# capsenseboard.net
KiCad netlist of a schematic drawn in EAGLE
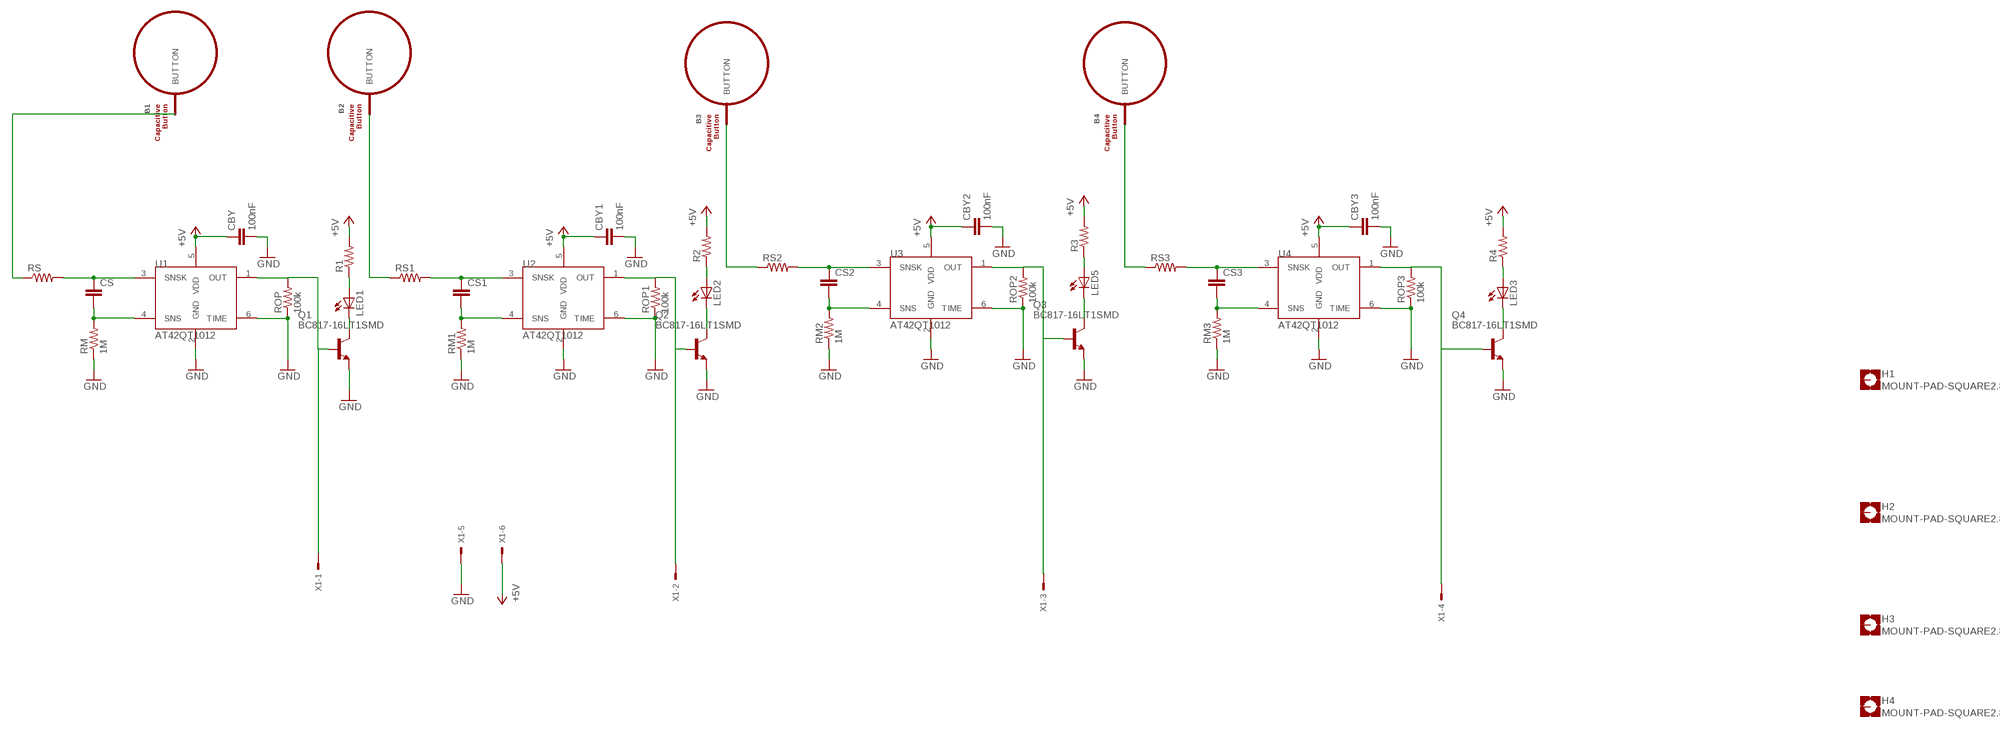
[diagram p0: schematic, sheet 1]

(export (version "E")
  (design (tool "Eeschema 10.0.6"))
  (components
    (comp (ref "B1")
      (value "BUTTON_PASSIVE12MM")
      (footprint "eagle-import:BUTTON_PASSIVE_12MM")
      (libsource (lib "eagle-import") (part "BUTTON_PASSIVE12MM"))
    )
    (comp (ref "B2")
      (value "BUTTON_PASSIVE12MM")
      (footprint "eagle-import:BUTTON_PASSIVE_12MM")
      (libsource (lib "eagle-import") (part "BUTTON_PASSIVE12MM"))
    )
    (comp (ref "B3")
      (value "BUTTON_PASSIVE12MM")
      (footprint "eagle-import:BUTTON_PASSIVE_12MM")
      (libsource (lib "eagle-import") (part "BUTTON_PASSIVE12MM"))
    )
    (comp (ref "B4")
      (value "BUTTON_PASSIVE12MM")
      (footprint "eagle-import:BUTTON_PASSIVE_12MM")
      (libsource (lib "eagle-import") (part "BUTTON_PASSIVE12MM"))
    )
    (comp (ref "CBY")
      (value "100nF")
      (footprint "eagle-import:C1206K")
      (libsource (lib "eagle-import") (part "C-EUC1206K"))
    )
    (comp (ref "CBY1")
      (value "100nF")
      (footprint "eagle-import:C1206K")
      (libsource (lib "eagle-import") (part "C-EUC1206K"))
    )
    (comp (ref "CBY2")
      (value "100nF")
      (footprint "eagle-import:C1206K")
      (libsource (lib "eagle-import") (part "C-EUC1206K"))
    )
    (comp (ref "CBY3")
      (value "100nF")
      (footprint "eagle-import:C1206K")
      (libsource (lib "eagle-import") (part "C-EUC1206K"))
    )
    (comp (ref "CS")
      (value "C-EUC1206K")
      (footprint "eagle-import:C1206K")
      (libsource (lib "eagle-import") (part "C-EUC1206K"))
    )
    (comp (ref "CS1")
      (value "C-EUC1206K")
      (footprint "eagle-import:C1206K")
      (libsource (lib "eagle-import") (part "C-EUC1206K"))
    )
    (comp (ref "CS2")
      (value "C-EUC1206K")
      (footprint "eagle-import:C1206K")
      (libsource (lib "eagle-import") (part "C-EUC1206K"))
    )
    (comp (ref "CS3")
      (value "C-EUC1206K")
      (footprint "eagle-import:C1206K")
      (libsource (lib "eagle-import") (part "C-EUC1206K"))
    )
    (comp (ref "H1")
      (value "MOUNT-PAD-SQUARE2.8")
      (footprint "eagle-import:2,8-PAD-SQUARE")
      (libsource (lib "eagle-import") (part "MOUNT-PAD-SQUARE2.8"))
    )
    (comp (ref "H2")
      (value "MOUNT-PAD-SQUARE2.8")
      (footprint "eagle-import:2,8-PAD-SQUARE")
      (libsource (lib "eagle-import") (part "MOUNT-PAD-SQUARE2.8"))
    )
    (comp (ref "H3")
      (value "MOUNT-PAD-SQUARE2.8")
      (footprint "eagle-import:2,8-PAD-SQUARE")
      (libsource (lib "eagle-import") (part "MOUNT-PAD-SQUARE2.8"))
    )
    (comp (ref "H4")
      (value "MOUNT-PAD-SQUARE2.8")
      (footprint "eagle-import:2,8-PAD-SQUARE")
      (libsource (lib "eagle-import") (part "MOUNT-PAD-SQUARE2.8"))
    )
    (comp (ref "LED1")
      (value "LEDCHIPLED_1206")
      (footprint "eagle-import:CHIPLED_1206")
      (libsource (lib "eagle-import") (part "LEDCHIPLED_1206"))
    )
    (comp (ref "LED2")
      (value "LEDCHIPLED_1206")
      (footprint "eagle-import:CHIPLED_1206")
      (libsource (lib "eagle-import") (part "LEDCHIPLED_1206"))
    )
    (comp (ref "LED3")
      (value "LEDCHIPLED_1206")
      (footprint "eagle-import:CHIPLED_1206")
      (libsource (lib "eagle-import") (part "LEDCHIPLED_1206"))
    )
    (comp (ref "LED5")
      (value "LEDCHIPLED_1206")
      (footprint "eagle-import:CHIPLED_1206")
      (libsource (lib "eagle-import") (part "LEDCHIPLED_1206"))
    )
    (comp (ref "Q1")
      (value "BC817-16LT1SMD")
      (footprint "eagle-import:SOT23-BEC")
      (libsource (lib "eagle-import") (part "BC817SMD-16LT1"))
    )
    (comp (ref "Q2")
      (value "BC817-16LT1SMD")
      (footprint "eagle-import:SOT23-BEC")
      (libsource (lib "eagle-import") (part "BC817SMD-16LT1"))
    )
    (comp (ref "Q3")
      (value "BC817-16LT1SMD")
      (footprint "eagle-import:SOT23-BEC")
      (libsource (lib "eagle-import") (part "BC817SMD-16LT1"))
    )
    (comp (ref "Q4")
      (value "BC817-16LT1SMD")
      (footprint "eagle-import:SOT23-BEC")
      (libsource (lib "eagle-import") (part "BC817SMD-16LT1"))
    )
    (comp (ref "R1")
      (value "R-US_R1206")
      (footprint "eagle-import:R1206")
      (libsource (lib "eagle-import") (part "R-US_R1206"))
    )
    (comp (ref "R2")
      (value "R-US_R1206")
      (footprint "eagle-import:R1206")
      (libsource (lib "eagle-import") (part "R-US_R1206"))
    )
    (comp (ref "R3")
      (value "R-US_R1206")
      (footprint "eagle-import:R1206")
      (libsource (lib "eagle-import") (part "R-US_R1206"))
    )
    (comp (ref "R4")
      (value "R-US_R1206")
      (footprint "eagle-import:R1206")
      (libsource (lib "eagle-import") (part "R-US_R1206"))
    )
    (comp (ref "RM")
      (value "1M")
      (footprint "eagle-import:R1206")
      (libsource (lib "eagle-import") (part "R-US_R1206"))
    )
    (comp (ref "RM1")
      (value "1M")
      (footprint "eagle-import:R1206")
      (libsource (lib "eagle-import") (part "R-US_R1206"))
    )
    (comp (ref "RM2")
      (value "1M")
      (footprint "eagle-import:R1206")
      (libsource (lib "eagle-import") (part "R-US_R1206"))
    )
    (comp (ref "RM3")
      (value "1M")
      (footprint "eagle-import:R1206")
      (libsource (lib "eagle-import") (part "R-US_R1206"))
    )
    (comp (ref "ROP")
      (value "100k")
      (footprint "eagle-import:R1206")
      (libsource (lib "eagle-import") (part "R-US_R1206"))
    )
    (comp (ref "ROP1")
      (value "100k")
      (footprint "eagle-import:R1206")
      (libsource (lib "eagle-import") (part "R-US_R1206"))
    )
    (comp (ref "ROP2")
      (value "100k")
      (footprint "eagle-import:R1206")
      (libsource (lib "eagle-import") (part "R-US_R1206"))
    )
    (comp (ref "ROP3")
      (value "100k")
      (footprint "eagle-import:R1206")
      (libsource (lib "eagle-import") (part "R-US_R1206"))
    )
    (comp (ref "RS")
      (value "R-US_R1206")
      (footprint "eagle-import:R1206")
      (libsource (lib "eagle-import") (part "R-US_R1206"))
    )
    (comp (ref "RS1")
      (value "R-US_R1206")
      (footprint "eagle-import:R1206")
      (libsource (lib "eagle-import") (part "R-US_R1206"))
    )
    (comp (ref "RS2")
      (value "R-US_R1206")
      (footprint "eagle-import:R1206")
      (libsource (lib "eagle-import") (part "R-US_R1206"))
    )
    (comp (ref "RS3")
      (value "R-US_R1206")
      (footprint "eagle-import:R1206")
      (libsource (lib "eagle-import") (part "R-US_R1206"))
    )
    (comp (ref "U1")
      (value "AT42QT1012")
      (footprint "eagle-import:SOT-23-6")
      (libsource (lib "eagle-import") (part "AT42QT1012"))
    )
    (comp (ref "U2")
      (value "AT42QT1012")
      (footprint "eagle-import:SOT-23-6")
      (libsource (lib "eagle-import") (part "AT42QT1012"))
    )
    (comp (ref "U3")
      (value "AT42QT1012")
      (footprint "eagle-import:SOT-23-6")
      (libsource (lib "eagle-import") (part "AT42QT1012"))
    )
    (comp (ref "U4")
      (value "AT42QT1012")
      (footprint "eagle-import:SOT-23-6")
      (libsource (lib "eagle-import") (part "AT42QT1012"))
    )
    (comp (ref "X1")
      (value "22-23-2061")
      (footprint "eagle-import:22-23-2061")
      (fields (field (name "MF") "MOLEX"))
      (libsource (lib "eagle-import") (part "22-23-2061"))
    )
  )
  (nets
    (net (code "1") (name "+5V") (class "Default")
      (node (ref "CBY") (pin "1") (pinfunction "1_1") (pintype "passive"))
      (node (ref "CBY1") (pin "1") (pinfunction "1_1") (pintype "passive"))
      (node (ref "CBY2") (pin "1") (pinfunction "1_1") (pintype "passive"))
      (node (ref "CBY3") (pin "1") (pinfunction "1_1") (pintype "passive"))
      (node (ref "R1") (pin "2") (pinfunction "2_2") (pintype "passive"))
      (node (ref "R2") (pin "2") (pinfunction "2_2") (pintype "passive"))
      (node (ref "R3") (pin "2") (pinfunction "2_2") (pintype "passive"))
      (node (ref "R4") (pin "2") (pinfunction "2_2") (pintype "passive"))
      (node (ref "U1") (pin "5") (pinfunction "VDD_5") (pintype "bidirectional"))
      (node (ref "U2") (pin "5") (pinfunction "VDD_5") (pintype "bidirectional"))
      (node (ref "U3") (pin "5") (pinfunction "VDD_5") (pintype "bidirectional"))
      (node (ref "U4") (pin "5") (pinfunction "VDD_5") (pintype "bidirectional"))
      (node (ref "X1") (pin "6") (pinfunction "S_6") (pintype "passive"))
    )
    (net (code "2") (name "GND") (class "Default")
      (node (ref "CBY") (pin "2") (pinfunction "2_2") (pintype "passive"))
      (node (ref "CBY1") (pin "2") (pinfunction "2_2") (pintype "passive"))
      (node (ref "CBY2") (pin "2") (pinfunction "2_2") (pintype "passive"))
      (node (ref "CBY3") (pin "2") (pinfunction "2_2") (pintype "passive"))
      (node (ref "Q1") (pin "E") (pinfunction "E_E") (pintype "passive"))
      (node (ref "Q2") (pin "E") (pinfunction "E_E") (pintype "passive"))
      (node (ref "Q3") (pin "E") (pinfunction "E_E") (pintype "passive"))
      (node (ref "Q4") (pin "E") (pinfunction "E_E") (pintype "passive"))
      (node (ref "RM") (pin "1") (pinfunction "1_1") (pintype "passive"))
      (node (ref "RM1") (pin "1") (pinfunction "1_1") (pintype "passive"))
      (node (ref "RM2") (pin "1") (pinfunction "1_1") (pintype "passive"))
      (node (ref "RM3") (pin "1") (pinfunction "1_1") (pintype "passive"))
      (node (ref "ROP") (pin "1") (pinfunction "1_1") (pintype "passive"))
      (node (ref "ROP1") (pin "1") (pinfunction "1_1") (pintype "passive"))
      (node (ref "ROP2") (pin "1") (pinfunction "1_1") (pintype "passive"))
      (node (ref "ROP3") (pin "1") (pinfunction "1_1") (pintype "passive"))
      (node (ref "U1") (pin "2") (pinfunction "GND_2") (pintype "bidirectional"))
      (node (ref "U1") (pin "6") (pinfunction "TIME_6") (pintype "bidirectional"))
      (node (ref "U2") (pin "2") (pinfunction "GND_2") (pintype "bidirectional"))
      (node (ref "U2") (pin "6") (pinfunction "TIME_6") (pintype "bidirectional"))
      (node (ref "U3") (pin "2") (pinfunction "GND_2") (pintype "bidirectional"))
      (node (ref "U3") (pin "6") (pinfunction "TIME_6") (pintype "bidirectional"))
      (node (ref "U4") (pin "2") (pinfunction "GND_2") (pintype "bidirectional"))
      (node (ref "U4") (pin "6") (pinfunction "TIME_6") (pintype "bidirectional"))
      (node (ref "X1") (pin "5") (pinfunction "S_5") (pintype "passive"))
    )
    (net (code "3") (name "Net-(B1-PadBUTTON)") (class "Default")
      (node (ref "B1") (pin "BUTTON") (pinfunction "BUTTON_BUTTON") (pintype "passive"))
      (node (ref "RS") (pin "1") (pinfunction "1_1") (pintype "passive"))
    )
    (net (code "4") (name "Net-(B2-PadBUTTON)") (class "Default")
      (node (ref "B2") (pin "BUTTON") (pinfunction "BUTTON_BUTTON") (pintype "passive"))
      (node (ref "RS1") (pin "1") (pinfunction "1_1") (pintype "passive"))
    )
    (net (code "5") (name "Net-(B3-PadBUTTON)") (class "Default")
      (node (ref "B3") (pin "BUTTON") (pinfunction "BUTTON_BUTTON") (pintype "passive"))
      (node (ref "RS2") (pin "1") (pinfunction "1_1") (pintype "passive"))
    )
    (net (code "6") (name "Net-(B4-PadBUTTON)") (class "Default")
      (node (ref "B4") (pin "BUTTON") (pinfunction "BUTTON_BUTTON") (pintype "passive"))
      (node (ref "RS3") (pin "1") (pinfunction "1_1") (pintype "passive"))
    )
    (net (code "7") (name "Net-(LED1-PadA)") (class "Default")
      (node (ref "LED1") (pin "A") (pinfunction "A_A") (pintype "passive"))
      (node (ref "R1") (pin "1") (pinfunction "1_1") (pintype "passive"))
    )
    (net (code "8") (name "Net-(LED1-PadC)") (class "Default")
      (node (ref "LED1") (pin "C") (pinfunction "C_C") (pintype "passive"))
      (node (ref "Q1") (pin "C") (pinfunction "C_C") (pintype "passive"))
    )
    (net (code "9") (name "Net-(LED2-PadA)") (class "Default")
      (node (ref "LED2") (pin "A") (pinfunction "A_A") (pintype "passive"))
      (node (ref "R2") (pin "1") (pinfunction "1_1") (pintype "passive"))
    )
    (net (code "10") (name "Net-(LED2-PadC)") (class "Default")
      (node (ref "LED2") (pin "C") (pinfunction "C_C") (pintype "passive"))
      (node (ref "Q2") (pin "C") (pinfunction "C_C") (pintype "passive"))
    )
    (net (code "11") (name "Net-(LED3-PadA)") (class "Default")
      (node (ref "LED3") (pin "A") (pinfunction "A_A") (pintype "passive"))
      (node (ref "R4") (pin "1") (pinfunction "1_1") (pintype "passive"))
    )
    (net (code "12") (name "Net-(LED3-PadC)") (class "Default")
      (node (ref "LED3") (pin "C") (pinfunction "C_C") (pintype "passive"))
      (node (ref "Q4") (pin "C") (pinfunction "C_C") (pintype "passive"))
    )
    (net (code "13") (name "Net-(LED5-PadA)") (class "Default")
      (node (ref "LED5") (pin "A") (pinfunction "A_A") (pintype "passive"))
      (node (ref "R3") (pin "1") (pinfunction "1_1") (pintype "passive"))
    )
    (net (code "14") (name "Net-(LED5-PadC)") (class "Default")
      (node (ref "LED5") (pin "C") (pinfunction "C_C") (pintype "passive"))
      (node (ref "Q3") (pin "C") (pinfunction "C_C") (pintype "passive"))
    )
    (net (code "15") (name "Net-(U1-OUT)") (class "Default")
      (node (ref "Q1") (pin "B") (pinfunction "B_B") (pintype "passive"))
      (node (ref "ROP") (pin "2") (pinfunction "2_2") (pintype "passive"))
      (node (ref "U1") (pin "1") (pinfunction "OUT_1") (pintype "bidirectional"))
      (node (ref "X1") (pin "1") (pinfunction "S_1") (pintype "passive"))
    )
    (net (code "16") (name "Net-(U1-SNS)") (class "Default")
      (node (ref "CS") (pin "2") (pinfunction "2_2") (pintype "passive"))
      (node (ref "RM") (pin "2") (pinfunction "2_2") (pintype "passive"))
      (node (ref "U1") (pin "4") (pinfunction "SNS_4") (pintype "bidirectional"))
    )
    (net (code "17") (name "Net-(U1-SNSK)") (class "Default")
      (node (ref "CS") (pin "1") (pinfunction "1_1") (pintype "passive"))
      (node (ref "RS") (pin "2") (pinfunction "2_2") (pintype "passive"))
      (node (ref "U1") (pin "3") (pinfunction "SNSK_3") (pintype "bidirectional"))
    )
    (net (code "18") (name "Net-(U2-OUT)") (class "Default")
      (node (ref "Q2") (pin "B") (pinfunction "B_B") (pintype "passive"))
      (node (ref "ROP1") (pin "2") (pinfunction "2_2") (pintype "passive"))
      (node (ref "U2") (pin "1") (pinfunction "OUT_1") (pintype "bidirectional"))
      (node (ref "X1") (pin "2") (pinfunction "S_2") (pintype "passive"))
    )
    (net (code "19") (name "Net-(U2-SNS)") (class "Default")
      (node (ref "CS1") (pin "2") (pinfunction "2_2") (pintype "passive"))
      (node (ref "RM1") (pin "2") (pinfunction "2_2") (pintype "passive"))
      (node (ref "U2") (pin "4") (pinfunction "SNS_4") (pintype "bidirectional"))
    )
    (net (code "20") (name "Net-(U2-SNSK)") (class "Default")
      (node (ref "CS1") (pin "1") (pinfunction "1_1") (pintype "passive"))
      (node (ref "RS1") (pin "2") (pinfunction "2_2") (pintype "passive"))
      (node (ref "U2") (pin "3") (pinfunction "SNSK_3") (pintype "bidirectional"))
    )
    (net (code "21") (name "Net-(U3-OUT)") (class "Default")
      (node (ref "Q3") (pin "B") (pinfunction "B_B") (pintype "passive"))
      (node (ref "ROP2") (pin "2") (pinfunction "2_2") (pintype "passive"))
      (node (ref "U3") (pin "1") (pinfunction "OUT_1") (pintype "bidirectional"))
      (node (ref "X1") (pin "3") (pinfunction "S_3") (pintype "passive"))
    )
    (net (code "22") (name "Net-(U3-SNS)") (class "Default")
      (node (ref "CS2") (pin "2") (pinfunction "2_2") (pintype "passive"))
      (node (ref "RM2") (pin "2") (pinfunction "2_2") (pintype "passive"))
      (node (ref "U3") (pin "4") (pinfunction "SNS_4") (pintype "bidirectional"))
    )
    (net (code "23") (name "Net-(U3-SNSK)") (class "Default")
      (node (ref "CS2") (pin "1") (pinfunction "1_1") (pintype "passive"))
      (node (ref "RS2") (pin "2") (pinfunction "2_2") (pintype "passive"))
      (node (ref "U3") (pin "3") (pinfunction "SNSK_3") (pintype "bidirectional"))
    )
    (net (code "24") (name "Net-(U4-OUT)") (class "Default")
      (node (ref "Q4") (pin "B") (pinfunction "B_B") (pintype "passive"))
      (node (ref "ROP3") (pin "2") (pinfunction "2_2") (pintype "passive"))
      (node (ref "U4") (pin "1") (pinfunction "OUT_1") (pintype "bidirectional"))
      (node (ref "X1") (pin "4") (pinfunction "S_4") (pintype "passive"))
    )
    (net (code "25") (name "Net-(U4-SNS)") (class "Default")
      (node (ref "CS3") (pin "2") (pinfunction "2_2") (pintype "passive"))
      (node (ref "RM3") (pin "2") (pinfunction "2_2") (pintype "passive"))
      (node (ref "U4") (pin "4") (pinfunction "SNS_4") (pintype "bidirectional"))
    )
    (net (code "26") (name "Net-(U4-SNSK)") (class "Default")
      (node (ref "CS3") (pin "1") (pinfunction "1_1") (pintype "passive"))
      (node (ref "RS3") (pin "2") (pinfunction "2_2") (pintype "passive"))
      (node (ref "U4") (pin "3") (pinfunction "SNSK_3") (pintype "bidirectional"))
    )
    (net (code "27") (name "unconnected-(H1-MOUNT-PadB2,8)") (class "Default")
      (node (ref "H1") (pin "B2,8") (pinfunction "MOUNT_B2,8") (pintype "passive"))
    )
    (net (code "28") (name "unconnected-(H2-MOUNT-PadB2,8)") (class "Default")
      (node (ref "H2") (pin "B2,8") (pinfunction "MOUNT_B2,8") (pintype "passive"))
    )
    (net (code "29") (name "unconnected-(H3-MOUNT-PadB2,8)") (class "Default")
      (node (ref "H3") (pin "B2,8") (pinfunction "MOUNT_B2,8") (pintype "passive"))
    )
    (net (code "30") (name "unconnected-(H4-MOUNT-PadB2,8)") (class "Default")
      (node (ref "H4") (pin "B2,8") (pinfunction "MOUNT_B2,8") (pintype "passive"))
    )
  )
)
